# BC28-NBIOT-V0_2.net
KiCad netlist of a schematic drawn in Altium Designer
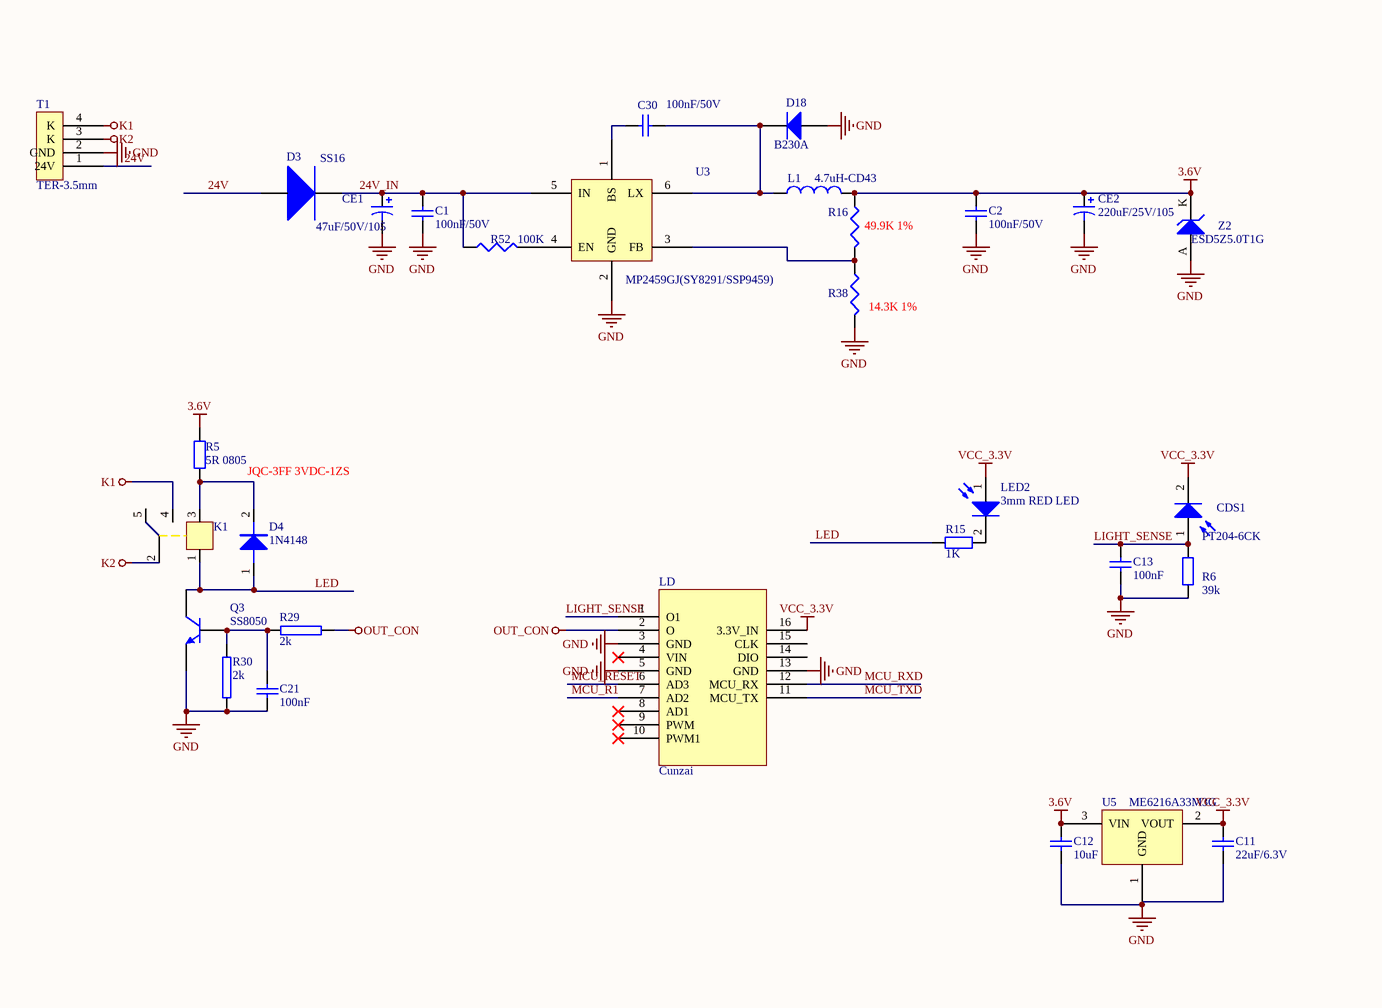
[diagram p0: BC28-NBIOT-V0.2.schdoc, left]
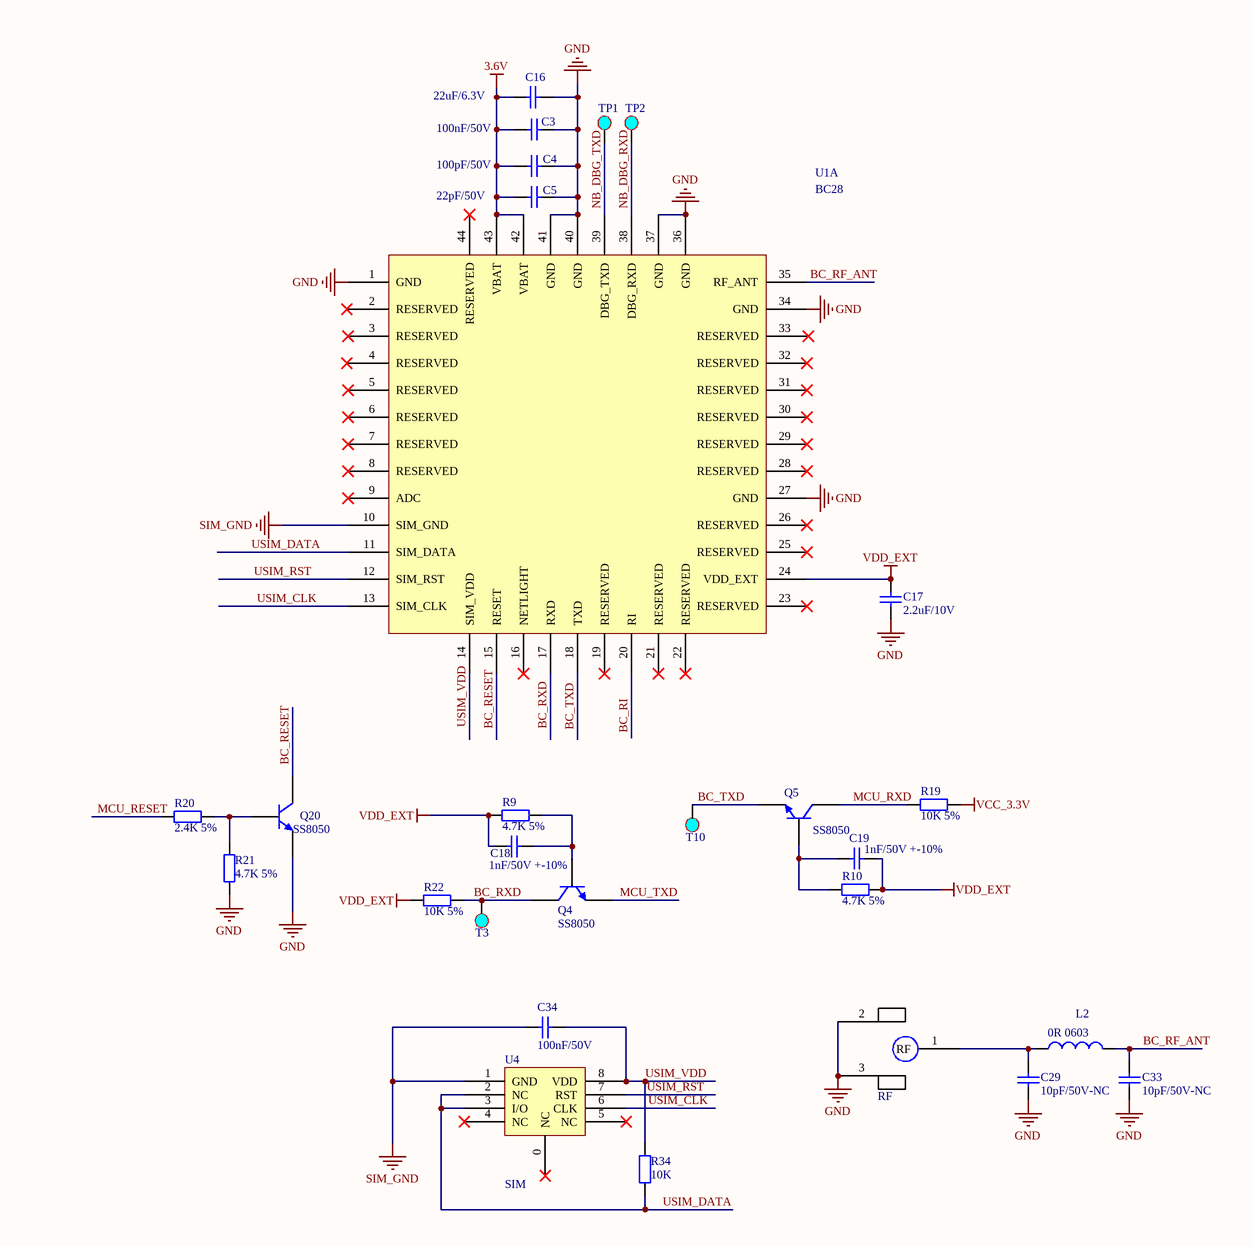
[diagram p1: BC28-NBIOT-V0.2.schdoc, right]

(export (version "E")
  (design (tool "Eeschema 10.0.6"))
  (components
    (comp (ref "C1")
      (value "100nF/50V")
      (footprint "0603")
      (description "Capacitor (Semiconductor SIM Model)")
      (fields (field (name "PUBLISHER") "Altium Limited"))
      (libsource (lib "Miscellaneous Devices") (part "Cap Semi"))
    )
    (comp (ref "C2")
      (value "100nF/50V")
      (footprint "0603")
      (description "Capacitor (Semiconductor SIM Model)")
      (fields (field (name "PUBLISHER") "Altium Limited"))
      (libsource (lib "Miscellaneous Devices") (part "Cap Semi"))
    )
    (comp (ref "C3")
      (value "100nF/50V")
      (footprint "0603")
      (description "Capacitor (Semiconductor SIM Model)")
      (fields (field (name "PUBLISHER") "Altium Limited"))
      (libsource (lib "Miscellaneous Devices") (part "Cap Semi"))
    )
    (comp (ref "C4")
      (value "100pF/50V")
      (footprint "0603")
      (description "Capacitor (Semiconductor SIM Model)")
      (fields (field (name "PUBLISHER") "Altium Limited"))
      (libsource (lib "Miscellaneous Devices") (part "Cap Semi"))
    )
    (comp (ref "C5")
      (value "22pF/50V")
      (footprint "0603")
      (description "Capacitor (Semiconductor SIM Model)")
      (fields (field (name "PUBLISHER") "Altium Limited"))
      (libsource (lib "Miscellaneous Devices") (part "Cap Semi"))
    )
    (comp (ref "C11")
      (value "22uF/6.3V")
      (footprint "0603")
      (description "Capacitor")
      (fields (field (name "PUBLISHER") "Altium Limited"))
      (libsource (lib "Miscellaneous Devices") (part "Cap"))
    )
    (comp (ref "C12")
      (value "10uF")
      (footprint "0603")
      (description "Capacitor")
      (fields (field (name "PUBLISHER") "Altium Limited"))
      (libsource (lib "Miscellaneous Devices") (part "Cap"))
    )
    (comp (ref "C13")
      (value "100nF")
      (footprint "C0603")
      (description "Capacitor")
      (fields (field (name "PUBLISHER") "Altium Limited"))
      (libsource (lib "Miscellaneous Devices") (part "Cap"))
    )
    (comp (ref "C16")
      (value "22uF/6.3V")
      (footprint "0603")
      (description "Capacitor (Semiconductor SIM Model)")
      (fields (field (name "PUBLISHER") "Altium Limited"))
      (libsource (lib "Miscellaneous Devices") (part "Cap Semi"))
    )
    (comp (ref "C17")
      (value "2.2uF/10V")
      (footprint "C0603")
      (description "Capacitor")
      (fields (field (name "PUBLISHER") "Altium Limited"))
      (libsource (lib "Miscellaneous Devices") (part "Cap"))
    )
    (comp (ref "C18")
      (value "1nF/50V +-10%")
      (footprint "0603")
      (description "Capacitor (Semiconductor SIM Model)")
      (fields (field (name "PUBLISHER") "Altium Limited"))
      (libsource (lib "Miscellaneous Devices") (part "Cap Semi"))
    )
    (comp (ref "C19")
      (value "1nF/50V +-10%")
      (footprint "0603")
      (description "Capacitor (Semiconductor SIM Model)")
      (fields (field (name "PUBLISHER") "Altium Limited"))
      (libsource (lib "Miscellaneous Devices") (part "Cap Semi"))
    )
    (comp (ref "C21")
      (value "100nF")
      (footprint "C0603")
      (description "Capacitor")
      (fields (field (name "PUBLISHER") "Altium Limited"))
      (libsource (lib "Miscellaneous Devices") (part "Cap"))
    )
    (comp (ref "C29")
      (value "10pF/50V-NC")
      (footprint "0603")
      (description "Capacitor (Semiconductor SIM Model)")
      (fields (field (name "PUBLISHER") "Altium Limited"))
      (libsource (lib "Miscellaneous Devices") (part "Cap Semi"))
    )
    (comp (ref "C30")
      (value "100nF/50V")
      (footprint "0603")
      (description "Capacitor (Semiconductor SIM Model)")
      (fields (field (name "PUBLISHER") "Altium Limited"))
      (libsource (lib "Miscellaneous Devices") (part "Cap Semi"))
    )
    (comp (ref "C33")
      (value "10pF/50V-NC")
      (footprint "0603")
      (description "Capacitor (Semiconductor SIM Model)")
      (fields (field (name "PUBLISHER") "Altium Limited"))
      (libsource (lib "Miscellaneous Devices") (part "Cap Semi"))
    )
    (comp (ref "C34")
      (value "100nF/50V")
      (footprint "0603")
      (description "Capacitor (Semiconductor SIM Model)")
      (fields (field (name "PUBLISHER") "Altium Limited"))
      (libsource (lib "Miscellaneous Devices") (part "Cap Semi"))
    )
    (comp (ref "CDS1")
      (value "PT204-6CK")
      (footprint "LED-3MM")
      (description "Photosensitive Diode")
      (fields (field (name "PUBLISHER") "Altium Limited"))
      (libsource (lib "Miscellaneous Devices") (part "Photo Sen"))
    )
    (comp (ref "CE1")
      (value "47uF/50V/105")
      (footprint "DIPC6X12")
      (description "Polarized Capacitor (Radial)")
      (fields (field (name "PUBLISHER") "Altium Limited"))
      (libsource (lib "Miscellaneous Devices") (part "Cap Pol1"))
    )
    (comp (ref "CE2")
      (value "220uF/25V/105")
      (footprint "DIPC6X12")
      (description "Polarized Capacitor (Radial)")
      (fields (field (name "PUBLISHER") "Altium Limited"))
      (libsource (lib "Miscellaneous Devices") (part "Cap Pol1"))
    )
    (comp (ref "D3") (value "SS16") (footprint "SMA") (libsource (lib "微波红外双鉴电路") (part "SS14")))
    (comp (ref "D4")
      (value "1N4148")
      (footprint "SOD123")
      (description "Diode")
      (libsource (lib "*") (part "DIODE"))
    )
    (comp (ref "D18")
      (value "B230A")
      (footprint "SMA")
      (description "1 Amp General Purpose Rectifier")
      (fields (field (name "PUBLISHER") "Altium Limited"))
      (libsource (lib "Miscellaneous Devices") (part "Diode 1N4007"))
    )
    (comp (ref "K1") (value "JQC-3FF 3VDC-1ZS") (footprint "JQC-3FF") (libsource (lib "*") (part "JDQ")))
    (comp (ref "L1")
      (value "4.7uH-CD43")
      (footprint "CDRH3D16")
      (description "Inductor")
      (fields (field (name "PUBLISHER") "Altium Limited"))
      (libsource (lib "Miscellaneous Devices") (part "Inductor"))
    )
    (comp (ref "L2")
      (value "0R 0603")
      (footprint "0603")
      (description "Inductor")
      (fields (field (name "PUBLISHER") "Altium Limited"))
      (libsource (lib "") (part "Inductor_1"))
    )
    (comp (ref "LD")
      (value "Cunzai")
      (footprint "CUNZAI_816")
      (libsource (lib "BC28-NBIOT-TEST-V0.1") (part "Cunzai"))
    )
    (comp (ref "LED2")
      (value "3mm RED LED")
      (footprint "LED-3MM")
      (description "Photosensitive Diode")
      (fields (field (name "PUBLISHER") "Altium Limited"))
      (libsource (lib "Miscellaneous Devices") (part "Photo Sen"))
    )
    (comp (ref "Q3") (value "SS8050") (footprint "SOT-23") (libsource (lib "MYLIB") (part "S9014")))
    (comp (ref "Q4") (value "SS8050") (footprint "SOT-23") (libsource (lib "MYLIB") (part "S9014")))
    (comp (ref "Q5") (value "SS8050") (footprint "SOT-23") (libsource (lib "MYLIB") (part "S9014")))
    (comp (ref "Q20") (value "SS8050") (footprint "SOT-23") (libsource (lib "MYLIB") (part "S9014")))
    (comp (ref "R5")
      (value "5R 0805")
      (footprint "0805")
      (description "Resistor")
      (fields (field (name "Comment") "Res2") (field (name "PUBLISHER") "Altium Limited"))
      (libsource (lib "") (part "Res2_1"))
    )
    (comp (ref "R6")
      (value "39k")
      (footprint "R0603")
      (description "Resistor")
      (fields (field (name "Comment") "Res2") (field (name "PUBLISHER") "Altium Limited"))
      (libsource (lib "") (part "Res2_2"))
    )
    (comp (ref "R9")
      (value "4.7K 5%")
      (footprint "R0603")
      (description "Resistor")
      (fields (field (name "PUBLISHER") "Altium Limited"))
      (libsource (lib "Miscellaneous Devices") (part "Res2"))
    )
    (comp (ref "R10")
      (value "4.7K 5%")
      (footprint "R0603")
      (description "Resistor")
      (fields (field (name "PUBLISHER") "Altium Limited"))
      (libsource (lib "") (part "Res2_3"))
    )
    (comp (ref "R15")
      (value "1K")
      (footprint "R0603")
      (description "Resistor")
      (fields (field (name "Comment") "Res2") (field (name "PUBLISHER") "Altium Limited"))
      (libsource (lib "") (part "Res2_3"))
    )
    (comp (ref "R16")
      (value "49.9K 1%")
      (footprint "0603")
      (description "Resistor")
      (fields (field (name "PUBLISHER") "Altium Limited"))
      (libsource (lib "Miscellaneous Devices") (part "Res3"))
    )
    (comp (ref "R19")
      (value "10K 5%")
      (footprint "R0603")
      (description "Resistor")
      (fields (field (name "PUBLISHER") "Altium Limited"))
      (libsource (lib "") (part "Res2_3"))
    )
    (comp (ref "R20")
      (value "2.4K 5%")
      (footprint "R0603")
      (description "Resistor")
      (fields (field (name "PUBLISHER") "Altium Limited"))
      (libsource (lib "Miscellaneous Devices") (part "Res2"))
    )
    (comp (ref "R21")
      (value "4.7K 5%")
      (footprint "R0603")
      (description "Resistor")
      (fields (field (name "PUBLISHER") "Altium Limited"))
      (libsource (lib "") (part "Res2_2"))
    )
    (comp (ref "R22")
      (value "10K 5%")
      (footprint "R0603")
      (description "Resistor")
      (fields (field (name "PUBLISHER") "Altium Limited"))
      (libsource (lib "Miscellaneous Devices") (part "Res2"))
    )
    (comp (ref "R29") (value "2k") (footprint "SR0603") (libsource (lib "*") (part "RES")))
    (comp (ref "R30") (value "2k") (footprint "SR0603") (libsource (lib "*") (part "RES")))
    (comp (ref "R34")
      (value "10K")
      (footprint "R0603")
      (description "Resistor")
      (fields (field (name "PUBLISHER") "Altium Limited"))
      (libsource (lib "") (part "Res2_1"))
    )
    (comp (ref "R38")
      (value "14.3K 1%")
      (footprint "0603")
      (description "Resistor")
      (fields (field (name "PUBLISHER") "Altium Limited"))
      (libsource (lib "Miscellaneous Devices") (part "Res3"))
    )
    (comp (ref "R52")
      (value "100K")
      (footprint "0603")
      (description "Resistor")
      (fields (field (name "PUBLISHER") "Altium Limited"))
      (libsource (lib "Miscellaneous Devices") (part "Res3"))
    )
    (comp (ref "RF") (value "RF_SMD") (footprint "UFL") (libsource (lib "STM32") (part "RF_SMD")))
    (comp (ref "T1")
      (value "TER-3.5mm")
      (footprint "4-KKK")
      (libsource (lib "灯控模块-V3.3-(101&102&100-2)-24V-8位拨码") (part "TER-3.5mm"))
    )
    (comp (ref "T3")
      (value "~")
      (footprint "TestPoints")
      (description "TestPoints")
      (libsource (lib "标准原理图库（特种板）") (part "TestPoints"))
    )
    (comp (ref "T10")
      (value "~")
      (footprint "TestPoints")
      (description "TestPoints")
      (libsource (lib "标准原理图库（特种板）") (part "TestPoints"))
    )
    (comp (ref "TP1")
      (value "~")
      (footprint "TestPoints")
      (description "TestPoints")
      (libsource (lib "标准原理图库（特种板）") (part "TestPoints"))
    )
    (comp (ref "TP2")
      (value "~")
      (footprint "TestPoints")
      (description "TestPoints")
      (libsource (lib "标准原理图库（特种板）") (part "TestPoints"))
    )
    (comp (ref "U1")
      (value "BC28")
      (footprint "QUECTEL_BC28_PCB_FOOTPRINT_PROTEL&AD_20171213:BC28")
      (libsource (lib "Quectel_BC28_SCH_Part_Protel&AD_20171213") (part "BC28"))
    )
    (comp (ref "U3")
      (value "MP2459GJ(SY8291/SSP9459)")
      (footprint "SOT23-6")
      (libsource (lib "SPECIAL-L-V6.6") (part "SY8120B"))
    )
    (comp (ref "U4")
      (value "SIM")
      (footprint "DFN8")
      (libsource (lib "Quectel_BC28_SCH_Part_Protel&AD_20171213") (part "SIM"))
    )
    (comp (ref "U5") (value "ME6216A33M3G") (footprint "SOT-23") (libsource (lib "Schlib1") (part "SSP6206")))
    (comp (ref "Z2")
      (value "ESD5Z5.0T1G")
      (footprint "SOD323")
      (description "Zener Diode")
      (fields (field (name "PUBLISHER") "Altium Limited"))
      (libsource (lib "Miscellaneous Devices") (part "D Zener"))
    )
  )
  (nets
    (net (code "1") (name "/24V") (class "Default")
      (node (ref "D3") (pin "1") (pinfunction "B_1") (pintype "passive"))
      (node (ref "T1") (pin "1") (pinfunction "24V_1") (pintype "passive"))
    )
    (net (code "2") (name "/24V_IN") (class "Default")
      (node (ref "C1") (pin "2") (pinfunction "2_2") (pintype "passive"))
      (node (ref "CE1") (pin "1") (pinfunction "1_1") (pintype "passive"))
      (node (ref "D3") (pin "2") (pinfunction "C_2") (pintype "passive"))
      (node (ref "R52") (pin "1") (pinfunction "1_1") (pintype "passive"))
      (node (ref "U3") (pin "5") (pinfunction "IN_5") (pintype "passive"))
    )
    (net (code "3") (name "/BC_RESET") (class "Default")
      (node (ref "Q20") (pin "3") (pinfunction "C_3") (pintype "passive"))
      (node (ref "U1") (pin "15") (pinfunction "RESET_15") (pintype "passive"))
    )
    (net (code "4") (name "/BC_RF_ANT") (class "Default")
      (node (ref "C33") (pin "2") (pinfunction "2_2") (pintype "passive"))
      (node (ref "L2") (pin "1") (pinfunction "1_1") (pintype "passive"))
      (node (ref "U1") (pin "35") (pinfunction "RF_ANT_35") (pintype "passive"))
    )
    (net (code "5") (name "/BC_RI") (class "Default")
      (node (ref "U1") (pin "20") (pinfunction "RI_20") (pintype "passive"))
    )
    (net (code "6") (name "/BC_RXD") (class "Default")
      (node (ref "Q4") (pin "3") (pinfunction "C_3") (pintype "passive"))
      (node (ref "R22") (pin "2") (pinfunction "2_2") (pintype "passive"))
      (node (ref "T3") (pin "1") (pinfunction "1_1") (pintype "passive"))
      (node (ref "U1") (pin "17") (pinfunction "RXD_17") (pintype "passive"))
    )
    (net (code "7") (name "/BC_TXD") (class "Default")
      (node (ref "Q5") (pin "2") (pinfunction "E_2") (pintype "passive"))
      (node (ref "T10") (pin "1") (pinfunction "1_1") (pintype "passive"))
      (node (ref "U1") (pin "18") (pinfunction "TXD_18") (pintype "passive"))
    )
    (net (code "8") (name "/LED") (class "Default")
      (node (ref "D4") (pin "1") (pintype "passive"))
      (node (ref "K1") (pin "1") (pintype "passive"))
      (node (ref "Q3") (pin "3") (pinfunction "C_3") (pintype "passive"))
      (node (ref "R15") (pin "2") (pinfunction "2_2") (pintype "passive"))
    )
    (net (code "9") (name "/LIGHT_SENSE") (class "Default")
      (node (ref "C13") (pin "2") (pinfunction "2_2") (pintype "passive"))
      (node (ref "CDS1") (pin "1") (pinfunction "A_1") (pintype "passive"))
      (node (ref "LD") (pin "1") (pinfunction "O1_1") (pintype "passive"))
      (node (ref "R6") (pin "2") (pinfunction "2_2") (pintype "passive"))
    )
    (net (code "10") (name "/MCU_R1") (class "Default")
      (node (ref "LD") (pin "7") (pinfunction "AD2_7") (pintype "passive"))
    )
    (net (code "11") (name "/MCU_RESET") (class "Default")
      (node (ref "LD") (pin "6") (pinfunction "AD3_6") (pintype "passive"))
      (node (ref "R20") (pin "1") (pinfunction "1_1") (pintype "passive"))
    )
    (net (code "12") (name "/MCU_RXD") (class "Default")
      (node (ref "LD") (pin "12") (pinfunction "MCU_RX_12") (pintype "passive"))
      (node (ref "Q5") (pin "3") (pinfunction "C_3") (pintype "passive"))
      (node (ref "R19") (pin "2") (pinfunction "2_2") (pintype "passive"))
    )
    (net (code "13") (name "/MCU_TXD") (class "Default")
      (node (ref "LD") (pin "11") (pinfunction "MCU_TX_11") (pintype "passive"))
      (node (ref "Q4") (pin "2") (pinfunction "E_2") (pintype "passive"))
    )
    (net (code "14") (name "/NB_DBG_RXD") (class "Default")
      (node (ref "TP2") (pin "1") (pinfunction "1_1") (pintype "passive"))
      (node (ref "U1") (pin "38") (pinfunction "DBG_RXD_38") (pintype "passive"))
    )
    (net (code "15") (name "/NB_DBG_TXD") (class "Default")
      (node (ref "TP1") (pin "1") (pinfunction "1_1") (pintype "passive"))
      (node (ref "U1") (pin "39") (pinfunction "DBG_TXD_39") (pintype "passive"))
    )
    (net (code "16") (name "/USIM_CLK") (class "Default")
      (node (ref "U1") (pin "13") (pinfunction "SIM_CLK_13") (pintype "passive"))
      (node (ref "U4") (pin "6") (pinfunction "CLK_6") (pintype "passive"))
    )
    (net (code "17") (name "/USIM_DATA") (class "Default")
      (node (ref "R34") (pin "2") (pinfunction "2_2") (pintype "passive"))
      (node (ref "U1") (pin "11") (pinfunction "SIM_DATA_11") (pintype "passive"))
      (node (ref "U4") (pin "2") (pinfunction "NC_2") (pintype "passive"))
      (node (ref "U4") (pin "3") (pinfunction "I/O_3") (pintype "passive"))
    )
    (net (code "18") (name "/USIM_RST") (class "Default")
      (node (ref "U1") (pin "12") (pinfunction "SIM_RST_12") (pintype "passive"))
      (node (ref "U4") (pin "7") (pinfunction "RST_7") (pintype "passive"))
    )
    (net (code "19") (name "/USIM_VDD") (class "Default")
      (node (ref "C34") (pin "1") (pinfunction "1_1") (pintype "passive"))
      (node (ref "R34") (pin "1") (pinfunction "1_1") (pintype "passive"))
      (node (ref "U1") (pin "14") (pinfunction "SIM_VDD_14") (pintype "passive"))
      (node (ref "U4") (pin "8") (pinfunction "VDD_8") (pintype "passive"))
    )
    (net (code "20") (name "3.6V") (class "Default")
      (node (ref "C12") (pin "1") (pinfunction "1_1") (pintype "passive"))
      (node (ref "C16") (pin "1") (pinfunction "1_1") (pintype "passive"))
      (node (ref "C2") (pin "2") (pinfunction "2_2") (pintype "passive"))
      (node (ref "C3") (pin "2") (pinfunction "2_2") (pintype "passive"))
      (node (ref "C4") (pin "2") (pinfunction "2_2") (pintype "passive"))
      (node (ref "C5") (pin "2") (pinfunction "2_2") (pintype "passive"))
      (node (ref "CE2") (pin "1") (pinfunction "1_1") (pintype "passive"))
      (node (ref "L1") (pin "2") (pinfunction "2_2") (pintype "passive"))
      (node (ref "R16") (pin "1") (pinfunction "1_1") (pintype "passive"))
      (node (ref "R5") (pin "1") (pinfunction "1_1") (pintype "passive"))
      (node (ref "U1") (pin "42") (pinfunction "VBAT_42") (pintype "passive"))
      (node (ref "U1") (pin "43") (pinfunction "VBAT_43") (pintype "passive"))
      (node (ref "U5") (pin "3") (pinfunction "VIN_3") (pintype "passive"))
      (node (ref "Z2") (pin "K") (pinfunction "K_K") (pintype "passive"))
    )
    (net (code "21") (name "GND") (class "Default")
      (node (ref "C1") (pin "1") (pinfunction "1_1") (pintype "passive"))
      (node (ref "C11") (pin "2") (pinfunction "2_2") (pintype "passive"))
      (node (ref "C12") (pin "2") (pinfunction "2_2") (pintype "passive"))
      (node (ref "C13") (pin "1") (pinfunction "1_1") (pintype "passive"))
      (node (ref "C16") (pin "2") (pinfunction "2_2") (pintype "passive"))
      (node (ref "C17") (pin "2") (pinfunction "2_2") (pintype "passive"))
      (node (ref "C2") (pin "1") (pinfunction "1_1") (pintype "passive"))
      (node (ref "C21") (pin "2") (pinfunction "2_2") (pintype "passive"))
      (node (ref "C29") (pin "1") (pinfunction "1_1") (pintype "passive"))
      (node (ref "C3") (pin "1") (pinfunction "1_1") (pintype "passive"))
      (node (ref "C33") (pin "1") (pinfunction "1_1") (pintype "passive"))
      (node (ref "C4") (pin "1") (pinfunction "1_1") (pintype "passive"))
      (node (ref "C5") (pin "1") (pinfunction "1_1") (pintype "passive"))
      (node (ref "CE1") (pin "2") (pinfunction "2_2") (pintype "passive"))
      (node (ref "CE2") (pin "2") (pinfunction "2_2") (pintype "passive"))
      (node (ref "D18") (pin "1") (pinfunction "A_1") (pintype "passive"))
      (node (ref "LD") (pin "13") (pinfunction "GND_13") (pintype "passive"))
      (node (ref "LD") (pin "3") (pinfunction "GND_3") (pintype "passive"))
      (node (ref "LD") (pin "5") (pinfunction "GND_5") (pintype "passive"))
      (node (ref "Q20") (pin "2") (pinfunction "E_2") (pintype "passive"))
      (node (ref "Q3") (pin "2") (pinfunction "E_2") (pintype "passive"))
      (node (ref "R21") (pin "1") (pinfunction "1_1") (pintype "passive"))
      (node (ref "R30") (pin "1") (pinfunction "1_1") (pintype "passive"))
      (node (ref "R38") (pin "2") (pinfunction "2_2") (pintype "passive"))
      (node (ref "R6") (pin "1") (pinfunction "1_1") (pintype "passive"))
      (node (ref "RF") (pin "2") (pinfunction "GND_2") (pintype "passive"))
      (node (ref "RF") (pin "3") (pinfunction "GND_3") (pintype "passive"))
      (node (ref "T1") (pin "2") (pinfunction "GND_2") (pintype "passive"))
      (node (ref "U1") (pin "1") (pinfunction "GND_1") (pintype "passive"))
      (node (ref "U1") (pin "27") (pinfunction "GND_27") (pintype "passive"))
      (node (ref "U1") (pin "34") (pinfunction "GND_34") (pintype "passive"))
      (node (ref "U1") (pin "36") (pinfunction "GND_36") (pintype "passive"))
      (node (ref "U1") (pin "37") (pinfunction "GND_37") (pintype "passive"))
      (node (ref "U1") (pin "40") (pinfunction "GND_40") (pintype "passive"))
      (node (ref "U1") (pin "41") (pinfunction "GND_41") (pintype "passive"))
      (node (ref "U3") (pin "2") (pinfunction "GND_2") (pintype "passive"))
      (node (ref "U5") (pin "1") (pinfunction "GND_1") (pintype "passive"))
      (node (ref "Z2") (pin "A") (pinfunction "A_A") (pintype "passive"))
    )
    (net (code "22") (name "K1") (class "Default")
      (node (ref "K1") (pin "4") (pintype "passive"))
      (node (ref "T1") (pin "4") (pinfunction "K_4") (pintype "passive"))
    )
    (net (code "23") (name "K2") (class "Default")
      (node (ref "K1") (pin "2") (pintype "passive"))
      (node (ref "T1") (pin "3") (pinfunction "K_3") (pintype "passive"))
    )
    (net (code "24") (name "Net-(D4-Pad2)") (class "Default")
      (node (ref "D4") (pin "2") (pintype "passive"))
      (node (ref "K1") (pin "3") (pintype "passive"))
      (node (ref "R5") (pin "2") (pinfunction "2_2") (pintype "passive"))
    )
    (net (code "25") (name "Net-(D18-K)") (class "Default")
      (node (ref "C30") (pin "1") (pinfunction "1_1") (pintype "passive"))
      (node (ref "D18") (pin "2") (pinfunction "K_2") (pintype "passive"))
      (node (ref "L1") (pin "1") (pinfunction "1_1") (pintype "passive"))
      (node (ref "U3") (pin "6") (pinfunction "LX_6") (pintype "passive"))
    )
    (net (code "26") (name "Net-(LED2-K)") (class "Default")
      (node (ref "LED2") (pin "2") (pinfunction "K_2") (pintype "passive"))
      (node (ref "R15") (pin "1") (pinfunction "1_1") (pintype "passive"))
    )
    (net (code "27") (name "Net-(Q3-B)") (class "Default")
      (node (ref "C21") (pin "1") (pinfunction "1_1") (pintype "passive"))
      (node (ref "Q3") (pin "1") (pinfunction "B_1") (pintype "passive"))
      (node (ref "R29") (pin "1") (pinfunction "1_1") (pintype "passive"))
      (node (ref "R30") (pin "2") (pinfunction "2_2") (pintype "passive"))
    )
    (net (code "28") (name "Net-(Q4-B)") (class "Default")
      (node (ref "C18") (pin "1") (pinfunction "1_1") (pintype "passive"))
      (node (ref "Q4") (pin "1") (pinfunction "B_1") (pintype "passive"))
      (node (ref "R9") (pin "2") (pinfunction "2_2") (pintype "passive"))
    )
    (net (code "29") (name "Net-(Q5-B)") (class "Default")
      (node (ref "C19") (pin "1") (pinfunction "1_1") (pintype "passive"))
      (node (ref "Q5") (pin "1") (pinfunction "B_1") (pintype "passive"))
      (node (ref "R10") (pin "2") (pinfunction "2_2") (pintype "passive"))
    )
    (net (code "30") (name "Net-(Q20-B)") (class "Default")
      (node (ref "Q20") (pin "1") (pinfunction "B_1") (pintype "passive"))
      (node (ref "R20") (pin "2") (pinfunction "2_2") (pintype "passive"))
      (node (ref "R21") (pin "2") (pinfunction "2_2") (pintype "passive"))
    )
    (net (code "31") (name "Net-(RF-RF)") (class "Default")
      (node (ref "C29") (pin "2") (pinfunction "2_2") (pintype "passive"))
      (node (ref "L2") (pin "2") (pinfunction "2_2") (pintype "passive"))
      (node (ref "RF") (pin "1") (pinfunction "RF_1") (pintype "passive"))
    )
    (net (code "32") (name "Net-(U3-BS)") (class "Default")
      (node (ref "C30") (pin "2") (pinfunction "2_2") (pintype "passive"))
      (node (ref "U3") (pin "1") (pinfunction "BS_1") (pintype "passive"))
    )
    (net (code "33") (name "Net-(U3-EN)") (class "Default")
      (node (ref "R52") (pin "2") (pinfunction "2_2") (pintype "passive"))
      (node (ref "U3") (pin "4") (pinfunction "EN_4") (pintype "passive"))
    )
    (net (code "34") (name "Net-(U3-FB)") (class "Default")
      (node (ref "R16") (pin "2") (pinfunction "2_2") (pintype "passive"))
      (node (ref "R38") (pin "1") (pinfunction "1_1") (pintype "passive"))
      (node (ref "U3") (pin "3") (pinfunction "FB_3") (pintype "passive"))
    )
    (net (code "35") (name "OUT_CON") (class "Default")
      (node (ref "LD") (pin "2") (pinfunction "O_2") (pintype "passive"))
      (node (ref "R29") (pin "2") (pinfunction "2_2") (pintype "passive"))
    )
    (net (code "36") (name "SIM_GND") (class "Default")
      (node (ref "C34") (pin "2") (pinfunction "2_2") (pintype "passive"))
      (node (ref "U1") (pin "10") (pinfunction "SIM_GND_10") (pintype "passive"))
      (node (ref "U4") (pin "1") (pinfunction "GND_1") (pintype "passive"))
    )
    (net (code "37") (name "VCC_3.3V") (class "Default")
      (node (ref "C11") (pin "1") (pinfunction "1_1") (pintype "passive"))
      (node (ref "CDS1") (pin "2") (pinfunction "K_2") (pintype "passive"))
      (node (ref "LD") (pin "16") (pinfunction "3.3V_IN_16") (pintype "passive"))
      (node (ref "R19") (pin "1") (pinfunction "1_1") (pintype "passive"))
      (node (ref "U5") (pin "2") (pinfunction "VOUT_2") (pintype "passive"))
    )
    (net (code "38") (name "VDD_EXT") (class "Default")
      (node (ref "C17") (pin "1") (pinfunction "1_1") (pintype "passive"))
      (node (ref "C18") (pin "2") (pinfunction "2_2") (pintype "passive"))
      (node (ref "C19") (pin "2") (pinfunction "2_2") (pintype "passive"))
      (node (ref "R10") (pin "1") (pinfunction "1_1") (pintype "passive"))
      (node (ref "R22") (pin "1") (pinfunction "1_1") (pintype "passive"))
      (node (ref "R9") (pin "1") (pinfunction "1_1") (pintype "passive"))
      (node (ref "U1") (pin "24") (pinfunction "VDD_EXT_24") (pintype "passive"))
    )
    (net (code "39") (name "unconnected-(K1-Pad5)") (class "Default")
      (node (ref "K1") (pin "5") (pintype "passive"))
    )
    (net (code "40") (name "unconnected-(LD-AD1-Pad8)") (class "Default")
      (node (ref "LD") (pin "8") (pinfunction "AD1_8") (pintype "passive+no_connect"))
    )
    (net (code "41") (name "unconnected-(LD-CLK-Pad15)") (class "Default")
      (node (ref "LD") (pin "15") (pinfunction "CLK_15") (pintype "passive"))
    )
    (net (code "42") (name "unconnected-(LD-DIO-Pad14)") (class "Default")
      (node (ref "LD") (pin "14") (pinfunction "DIO_14") (pintype "passive"))
    )
    (net (code "43") (name "unconnected-(LD-PWM-Pad9)") (class "Default")
      (node (ref "LD") (pin "9") (pinfunction "PWM_9") (pintype "passive+no_connect"))
    )
    (net (code "44") (name "unconnected-(LD-PWM1-Pad10)") (class "Default")
      (node (ref "LD") (pin "10") (pinfunction "PWM1_10") (pintype "passive+no_connect"))
    )
    (net (code "45") (name "unconnected-(LD-VIN-Pad4)") (class "Default")
      (node (ref "LD") (pin "4") (pinfunction "VIN_4") (pintype "passive+no_connect"))
    )
    (net (code "46") (name "unconnected-(LED2-A-Pad1)") (class "Default")
      (node (ref "LED2") (pin "1") (pinfunction "A_1") (pintype "passive"))
    )
    (net (code "47") (name "unconnected-(U1A-ADC-Pad9)") (class "Default")
      (node (ref "U1") (pin "9") (pinfunction "ADC_9") (pintype "passive+no_connect"))
    )
    (net (code "48") (name "unconnected-(U1A-NETLIGHT-Pad16)") (class "Default")
      (node (ref "U1") (pin "16") (pinfunction "NETLIGHT_16") (pintype "passive+no_connect"))
    )
    (net (code "49") (name "unconnected-(U1A-RESERVED-Pad2)") (class "Default")
      (node (ref "U1") (pin "2") (pinfunction "RESERVED_2") (pintype "passive"))
    )
    (net (code "50") (name "unconnected-(U1A-RESERVED-Pad3)") (class "Default")
      (node (ref "U1") (pin "3") (pinfunction "RESERVED_3") (pintype "passive+no_connect"))
    )
    (net (code "51") (name "unconnected-(U1A-RESERVED-Pad4)") (class "Default")
      (node (ref "U1") (pin "4") (pinfunction "RESERVED_4") (pintype "passive"))
    )
    (net (code "52") (name "unconnected-(U1A-RESERVED-Pad5)") (class "Default")
      (node (ref "U1") (pin "5") (pinfunction "RESERVED_5") (pintype "passive+no_connect"))
    )
    (net (code "53") (name "unconnected-(U1A-RESERVED-Pad6)") (class "Default")
      (node (ref "U1") (pin "6") (pinfunction "RESERVED_6") (pintype "passive+no_connect"))
    )
    (net (code "54") (name "unconnected-(U1A-RESERVED-Pad7)") (class "Default")
      (node (ref "U1") (pin "7") (pinfunction "RESERVED_7") (pintype "passive+no_connect"))
    )
    (net (code "55") (name "unconnected-(U1A-RESERVED-Pad8)") (class "Default")
      (node (ref "U1") (pin "8") (pinfunction "RESERVED_8") (pintype "passive+no_connect"))
    )
    (net (code "56") (name "unconnected-(U1A-RESERVED-Pad19)") (class "Default")
      (node (ref "U1") (pin "19") (pinfunction "RESERVED_19") (pintype "passive+no_connect"))
    )
    (net (code "57") (name "unconnected-(U1A-RESERVED-Pad21)") (class "Default")
      (node (ref "U1") (pin "21") (pinfunction "RESERVED_21") (pintype "passive+no_connect"))
    )
    (net (code "58") (name "unconnected-(U1A-RESERVED-Pad22)") (class "Default")
      (node (ref "U1") (pin "22") (pinfunction "RESERVED_22") (pintype "passive+no_connect"))
    )
    (net (code "59") (name "unconnected-(U1A-RESERVED-Pad23)") (class "Default")
      (node (ref "U1") (pin "23") (pinfunction "RESERVED_23") (pintype "passive+no_connect"))
    )
    (net (code "60") (name "unconnected-(U1A-RESERVED-Pad25)") (class "Default")
      (node (ref "U1") (pin "25") (pinfunction "RESERVED_25") (pintype "passive+no_connect"))
    )
    (net (code "61") (name "unconnected-(U1A-RESERVED-Pad26)") (class "Default")
      (node (ref "U1") (pin "26") (pinfunction "RESERVED_26") (pintype "passive+no_connect"))
    )
    (net (code "62") (name "unconnected-(U1A-RESERVED-Pad28)") (class "Default")
      (node (ref "U1") (pin "28") (pinfunction "RESERVED_28") (pintype "passive+no_connect"))
    )
    (net (code "63") (name "unconnected-(U1A-RESERVED-Pad29)") (class "Default")
      (node (ref "U1") (pin "29") (pinfunction "RESERVED_29") (pintype "passive+no_connect"))
    )
    (net (code "64") (name "unconnected-(U1A-RESERVED-Pad30)") (class "Default")
      (node (ref "U1") (pin "30") (pinfunction "RESERVED_30") (pintype "passive+no_connect"))
    )
    (net (code "65") (name "unconnected-(U1A-RESERVED-Pad31)") (class "Default")
      (node (ref "U1") (pin "31") (pinfunction "RESERVED_31") (pintype "passive+no_connect"))
    )
    (net (code "66") (name "unconnected-(U1A-RESERVED-Pad32)") (class "Default")
      (node (ref "U1") (pin "32") (pinfunction "RESERVED_32") (pintype "passive+no_connect"))
    )
    (net (code "67") (name "unconnected-(U1A-RESERVED-Pad33)") (class "Default")
      (node (ref "U1") (pin "33") (pinfunction "RESERVED_33") (pintype "passive"))
    )
    (net (code "68") (name "unconnected-(U1A-RESERVED-Pad44)") (class "Default")
      (node (ref "U1") (pin "44") (pinfunction "RESERVED_44") (pintype "passive+no_connect"))
    )
    (net (code "69") (name "unconnected-(U4-NC-Pad0)") (class "Default")
      (node (ref "U4") (pin "0") (pinfunction "NC_0") (pintype "passive+no_connect"))
    )
    (net (code "70") (name "unconnected-(U4-NC-Pad4)") (class "Default")
      (node (ref "U4") (pin "4") (pinfunction "NC_4") (pintype "passive+no_connect"))
    )
    (net (code "71") (name "unconnected-(U4-NC-Pad5)") (class "Default")
      (node (ref "U4") (pin "5") (pinfunction "NC_5") (pintype "passive+no_connect"))
    )
  )
)
